# LineFollower.net
KiCad netlist of a schematic drawn in EAGLE
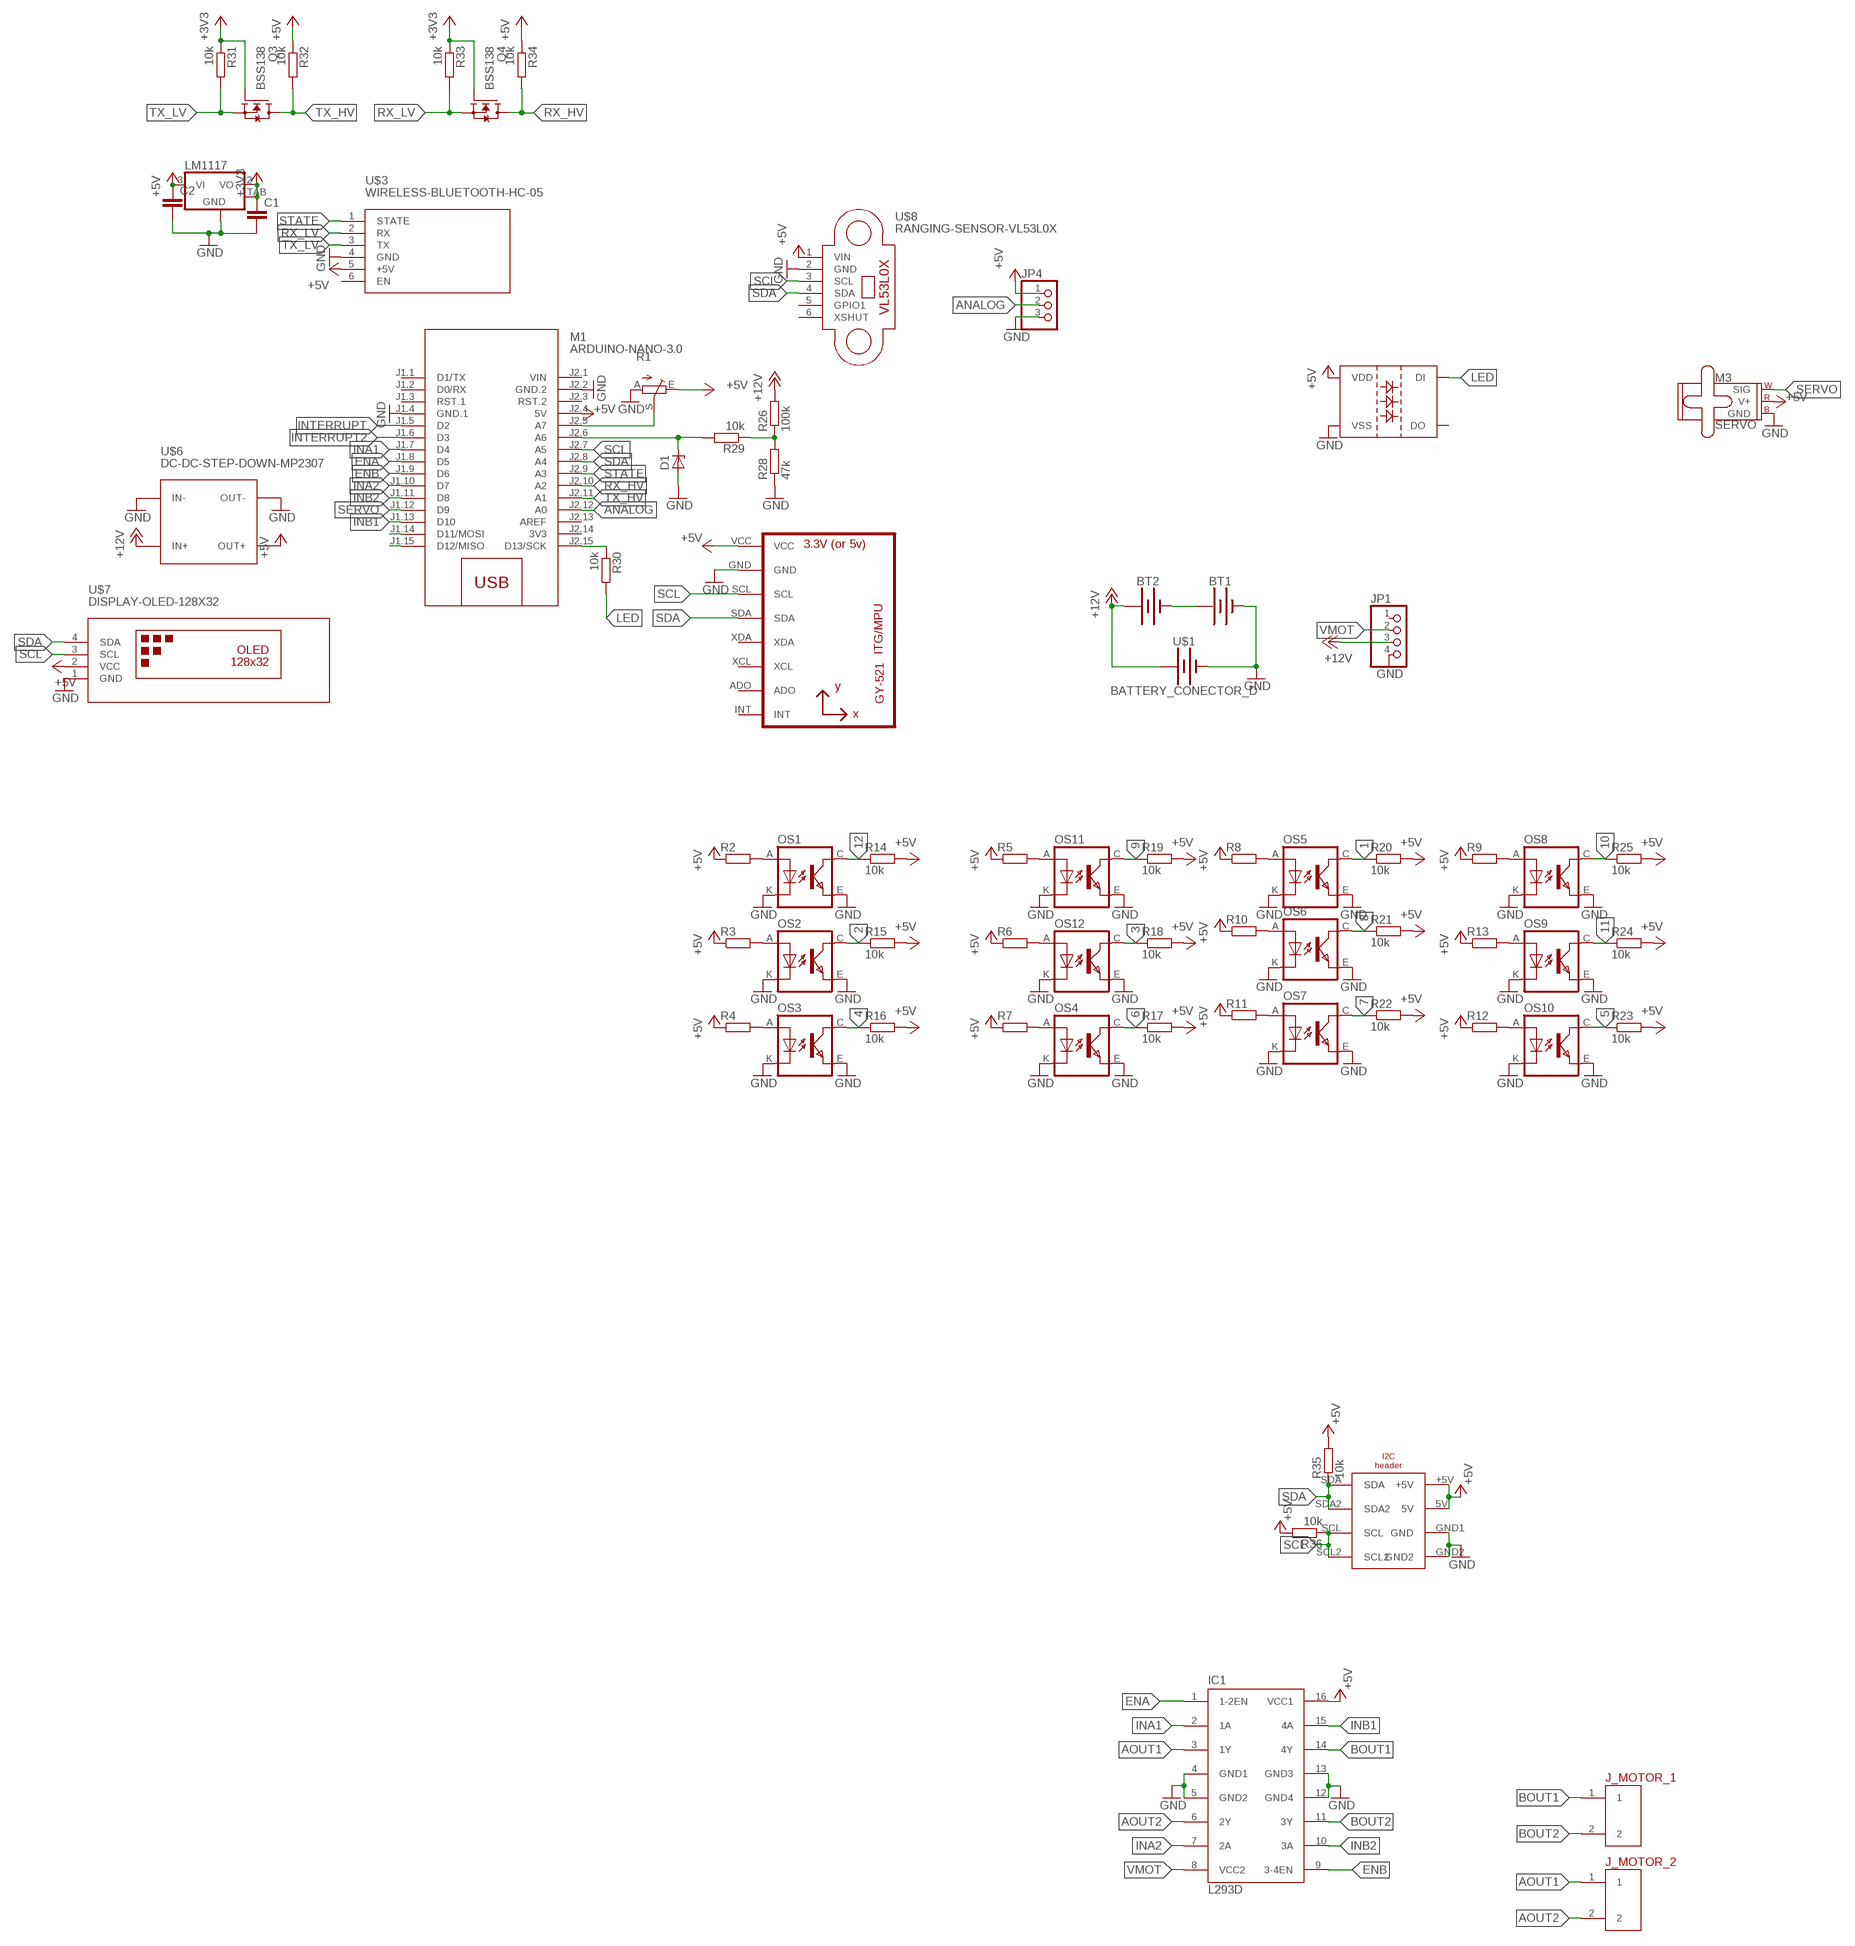
[diagram p0: schematic, sheet 1, part 1 of 2]
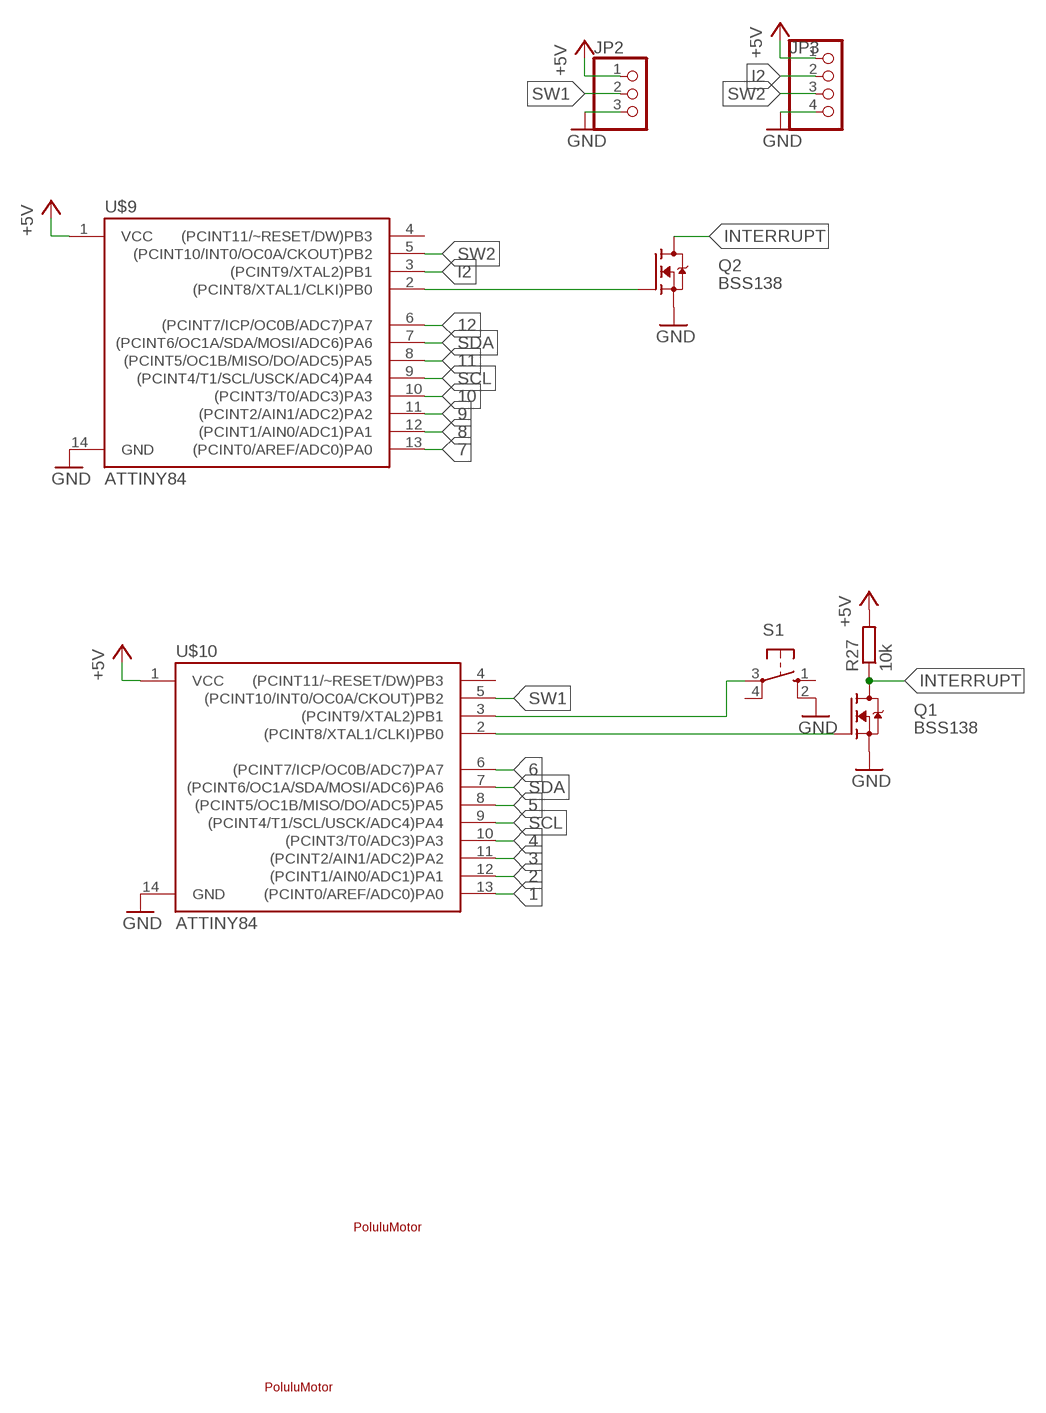
[diagram p1: schematic, sheet 1, part 2 of 2]

(export (version "E")
  (design (tool "Eeschema 10.0.6"))
  (components
    (comp (ref "BT1")
      (value "BATTERY-AA_KIT")
      (footprint "eagle-import:BATTERY-AA-KIT")
      (libsource (lib "eagle-import") (part "BATTERY-AA_KIT"))
    )
    (comp (ref "BT2")
      (value "BATTERY-AA_KIT")
      (footprint "eagle-import:BATTERY-AA-KIT")
      (libsource (lib "eagle-import") (part "BATTERY-AA_KIT"))
    )
    (comp (ref "C1")
      (value "C-EUC1206")
      (footprint "eagle-import:C1206")
      (libsource (lib "eagle-import") (part "C-EUC1206"))
    )
    (comp (ref "C2")
      (value "C-EUC1206")
      (footprint "eagle-import:C1206")
      (libsource (lib "eagle-import") (part "C-EUC1206"))
    )
    (comp (ref "D1")
      (value "ZENER-DIODESOD80C")
      (footprint "eagle-import:SOD80C")
      (libsource (lib "eagle-import") (part "ZENER-DIODESOD80C"))
    )
    (comp (ref "IC1")
      (value "L293D")
      (footprint "eagle-import:L293")
      (libsource (lib "eagle-import") (part "L293D"))
    )
    (comp (ref "JP1")
      (value "PINHD-1X4")
      (footprint "eagle-import:1X04")
      (libsource (lib "eagle-import") (part "PINHD-1X4"))
    )
    (comp (ref "JP2")
      (value "PINHD-1X3")
      (footprint "eagle-import:1X03")
      (libsource (lib "eagle-import") (part "PINHD-1X3"))
    )
    (comp (ref "JP3")
      (value "PINHD-1X4")
      (footprint "eagle-import:1X04")
      (libsource (lib "eagle-import") (part "PINHD-1X4"))
    )
    (comp (ref "JP4")
      (value "PINHD-1X3")
      (footprint "eagle-import:1X03")
      (libsource (lib "eagle-import") (part "PINHD-1X3"))
    )
    (comp (ref "J_MOTOR_1")
      (value "MOTOR_CONNECTOR")
      (footprint "eagle-import:MOTOR_CONNECTOR_FOOTPRINT")
      (libsource (lib "eagle-import") (part "MOTOR_CONNECTOR"))
    )
    (comp (ref "J_MOTOR_2")
      (value "MOTOR_CONNECTOR")
      (footprint "eagle-import:MOTOR_CONNECTOR_FOOTPRINT")
      (libsource (lib "eagle-import") (part "MOTOR_CONNECTOR"))
    )
    (comp (ref "LED1")
      (value "WS2812B")
      (footprint "eagle-import:WS2812B")
      (libsource (lib "eagle-import") (part "WS2812B"))
    )
    (comp (ref "M1")
      (value "ARDUINO-NANO-3.0")
      (footprint "eagle-import:ARDUINO-NANO-3.0")
      (libsource (lib "eagle-import") (part "ARDUINO-NANO-3.0"))
    )
    (comp (ref "M3")
      (value "SERVO")
      (footprint "eagle-import:1X03")
      (libsource (lib "eagle-import") (part "SERVO"))
    )
    (comp (ref "OS1")
      (value "TCRT5000")
      (footprint "eagle-import:TCRT5000")
      (libsource (lib "eagle-import") (part "TCRT5000"))
    )
    (comp (ref "OS2")
      (value "TCRT5000")
      (footprint "eagle-import:TCRT5000")
      (libsource (lib "eagle-import") (part "TCRT5000"))
    )
    (comp (ref "OS3")
      (value "TCRT5000")
      (footprint "eagle-import:TCRT5000")
      (libsource (lib "eagle-import") (part "TCRT5000"))
    )
    (comp (ref "OS4")
      (value "TCRT5000")
      (footprint "eagle-import:TCRT5000")
      (libsource (lib "eagle-import") (part "TCRT5000"))
    )
    (comp (ref "OS5")
      (value "TCRT5000")
      (footprint "eagle-import:TCRT5000")
      (libsource (lib "eagle-import") (part "TCRT5000"))
    )
    (comp (ref "OS6")
      (value "TCRT5000")
      (footprint "eagle-import:TCRT5000")
      (libsource (lib "eagle-import") (part "TCRT5000"))
    )
    (comp (ref "OS7")
      (value "TCRT5000")
      (footprint "eagle-import:TCRT5000")
      (libsource (lib "eagle-import") (part "TCRT5000"))
    )
    (comp (ref "OS8")
      (value "TCRT5000")
      (footprint "eagle-import:TCRT5000")
      (libsource (lib "eagle-import") (part "TCRT5000"))
    )
    (comp (ref "OS9")
      (value "TCRT5000")
      (footprint "eagle-import:TCRT5000")
      (libsource (lib "eagle-import") (part "TCRT5000"))
    )
    (comp (ref "OS10")
      (value "TCRT5000")
      (footprint "eagle-import:TCRT5000")
      (libsource (lib "eagle-import") (part "TCRT5000"))
    )
    (comp (ref "OS11")
      (value "TCRT5000")
      (footprint "eagle-import:TCRT5000")
      (libsource (lib "eagle-import") (part "TCRT5000"))
    )
    (comp (ref "OS12")
      (value "TCRT5000")
      (footprint "eagle-import:TCRT5000")
      (libsource (lib "eagle-import") (part "TCRT5000"))
    )
    (comp (ref "Q1")
      (value "BSS138")
      (footprint "eagle-import:SOT23")
      (fields (field (name "MF") "Fairchild"))
      (libsource (lib "eagle-import") (part "BSS138"))
    )
    (comp (ref "Q2")
      (value "BSS138")
      (footprint "eagle-import:SOT23")
      (fields (field (name "MF") "Fairchild"))
      (libsource (lib "eagle-import") (part "BSS138"))
    )
    (comp (ref "Q3")
      (value "BSS138")
      (footprint "eagle-import:SOT23")
      (fields (field (name "MF") "Fairchild"))
      (libsource (lib "eagle-import") (part "BSS138"))
    )
    (comp (ref "Q4")
      (value "BSS138")
      (footprint "eagle-import:SOT23")
      (fields (field (name "MF") "Fairchild"))
      (libsource (lib "eagle-import") (part "BSS138"))
    )
    (comp (ref "R1")
      (value "TRIM_EU-RJ9W")
      (footprint "eagle-import:RJ9W")
      (libsource (lib "eagle-import") (part "TRIM_EU-RJ9W"))
    )
    (comp (ref "R2")
      (value "R-EU_M1206")
      (footprint "eagle-import:M1206")
      (libsource (lib "eagle-import") (part "R-EU_M1206"))
    )
    (comp (ref "R3")
      (value "R-EU_M1206")
      (footprint "eagle-import:M1206")
      (libsource (lib "eagle-import") (part "R-EU_M1206"))
    )
    (comp (ref "R4")
      (value "R-EU_M1206")
      (footprint "eagle-import:M1206")
      (libsource (lib "eagle-import") (part "R-EU_M1206"))
    )
    (comp (ref "R5")
      (value "R-EU_M1206")
      (footprint "eagle-import:M1206")
      (libsource (lib "eagle-import") (part "R-EU_M1206"))
    )
    (comp (ref "R6")
      (value "R-EU_M1206")
      (footprint "eagle-import:M1206")
      (libsource (lib "eagle-import") (part "R-EU_M1206"))
    )
    (comp (ref "R7")
      (value "R-EU_M1206")
      (footprint "eagle-import:M1206")
      (libsource (lib "eagle-import") (part "R-EU_M1206"))
    )
    (comp (ref "R8")
      (value "R-EU_M1206")
      (footprint "eagle-import:M1206")
      (libsource (lib "eagle-import") (part "R-EU_M1206"))
    )
    (comp (ref "R9")
      (value "R-EU_M1206")
      (footprint "eagle-import:M1206")
      (libsource (lib "eagle-import") (part "R-EU_M1206"))
    )
    (comp (ref "R10")
      (value "R-EU_M1206")
      (footprint "eagle-import:M1206")
      (libsource (lib "eagle-import") (part "R-EU_M1206"))
    )
    (comp (ref "R11")
      (value "R-EU_M1206")
      (footprint "eagle-import:M1206")
      (libsource (lib "eagle-import") (part "R-EU_M1206"))
    )
    (comp (ref "R12")
      (value "R-EU_M1206")
      (footprint "eagle-import:M1206")
      (libsource (lib "eagle-import") (part "R-EU_M1206"))
    )
    (comp (ref "R13")
      (value "R-EU_M1206")
      (footprint "eagle-import:M1206")
      (libsource (lib "eagle-import") (part "R-EU_M1206"))
    )
    (comp (ref "R14")
      (value "10k")
      (footprint "eagle-import:M1206")
      (libsource (lib "eagle-import") (part "R-EU_M1206"))
    )
    (comp (ref "R15")
      (value "10k")
      (footprint "eagle-import:M1206")
      (libsource (lib "eagle-import") (part "R-EU_M1206"))
    )
    (comp (ref "R16")
      (value "10k")
      (footprint "eagle-import:M1206")
      (libsource (lib "eagle-import") (part "R-EU_M1206"))
    )
    (comp (ref "R17")
      (value "10k")
      (footprint "eagle-import:M1206")
      (libsource (lib "eagle-import") (part "R-EU_M1206"))
    )
    (comp (ref "R18")
      (value "10k")
      (footprint "eagle-import:M1206")
      (libsource (lib "eagle-import") (part "R-EU_M1206"))
    )
    (comp (ref "R19")
      (value "10k")
      (footprint "eagle-import:M1206")
      (libsource (lib "eagle-import") (part "R-EU_M1206"))
    )
    (comp (ref "R20")
      (value "10k")
      (footprint "eagle-import:M1206")
      (libsource (lib "eagle-import") (part "R-EU_M1206"))
    )
    (comp (ref "R21")
      (value "10k")
      (footprint "eagle-import:M1206")
      (libsource (lib "eagle-import") (part "R-EU_M1206"))
    )
    (comp (ref "R22")
      (value "10k")
      (footprint "eagle-import:M1206")
      (libsource (lib "eagle-import") (part "R-EU_M1206"))
    )
    (comp (ref "R23")
      (value "10k")
      (footprint "eagle-import:M1206")
      (libsource (lib "eagle-import") (part "R-EU_M1206"))
    )
    (comp (ref "R24")
      (value "10k")
      (footprint "eagle-import:M1206")
      (libsource (lib "eagle-import") (part "R-EU_M1206"))
    )
    (comp (ref "R25")
      (value "10k")
      (footprint "eagle-import:M1206")
      (libsource (lib "eagle-import") (part "R-EU_M1206"))
    )
    (comp (ref "R26")
      (value "100k")
      (footprint "eagle-import:M1206")
      (libsource (lib "eagle-import") (part "R-EU_M1206"))
    )
    (comp (ref "R27")
      (value "10k")
      (footprint "eagle-import:M1206")
      (libsource (lib "eagle-import") (part "R-EU_M1206"))
    )
    (comp (ref "R28")
      (value "47k")
      (footprint "eagle-import:M1206")
      (libsource (lib "eagle-import") (part "R-EU_M1206"))
    )
    (comp (ref "R29")
      (value "10k")
      (footprint "eagle-import:M1206")
      (libsource (lib "eagle-import") (part "R-EU_M1206"))
    )
    (comp (ref "R30")
      (value "10k")
      (footprint "eagle-import:M1206")
      (libsource (lib "eagle-import") (part "R-EU_M1206"))
    )
    (comp (ref "R31")
      (value "10k")
      (footprint "eagle-import:M1206")
      (libsource (lib "eagle-import") (part "R-EU_M1206"))
    )
    (comp (ref "R32")
      (value "10k")
      (footprint "eagle-import:M1206")
      (libsource (lib "eagle-import") (part "R-EU_M1206"))
    )
    (comp (ref "R33")
      (value "10k")
      (footprint "eagle-import:M1206")
      (libsource (lib "eagle-import") (part "R-EU_M1206"))
    )
    (comp (ref "R34")
      (value "10k")
      (footprint "eagle-import:M1206")
      (libsource (lib "eagle-import") (part "R-EU_M1206"))
    )
    (comp (ref "R35")
      (value "10k")
      (footprint "eagle-import:M1206")
      (libsource (lib "eagle-import") (part "R-EU_M1206"))
    )
    (comp (ref "R36")
      (value "10k")
      (footprint "eagle-import:M1206")
      (libsource (lib "eagle-import") (part "R-EU_M1206"))
    )
    (comp (ref "S1")
      (value "10-XX")
      (footprint "eagle-import:B3F-10XX")
      (fields (field (name "MPN") "B3F-1000"))
      (libsource (lib "eagle-import") (part "10-XX"))
    )
    (comp (ref "U$1")
      (value "BATTERY_CONECTOR_D")
      (footprint "eagle-import:BATTERY_CONECTOR_D")
      (libsource (lib "eagle-import") (part "BATTERY_CONECTOR_D"))
    )
    (comp (ref "U$2")
      (value "I2C_HEADER")
      (footprint "eagle-import:I2_HEADER")
      (libsource (lib "eagle-import") (part "I2C_HEADER"))
    )
    (comp (ref "U$3")
      (value "WIRELESS-BLUETOOTH-HC-05")
      (footprint "eagle-import:WIRELESS-BLUETOOTH-HC-05")
      (libsource (lib "eagle-import") (part "WIRELESS-BLUETOOTH-HC-05"))
    )
    (comp (ref "U$4")
      (value "LM1117")
      (footprint "eagle-import:LM1117")
      (libsource (lib "eagle-import") (part "LM1117"))
    )
    (comp (ref "U$6")
      (value "DC-DC-STEP-DOWN-MP2307")
      (footprint "eagle-import:DC-DC-STEP-DOWN-MP2307")
      (libsource (lib "eagle-import") (part "DC-DC-STEP-DOWN-MP2307"))
    )
    (comp (ref "U$7")
      (value "DISPLAY-OLED-128X32")
      (footprint "eagle-import:DISPLAY-OLED-128X32")
      (libsource (lib "eagle-import") (part "DISPLAY-OLED-128X32"))
    )
    (comp (ref "U$8")
      (value "RANGING-SENSOR-VL53L0X")
      (footprint "eagle-import:RANGING-SENSOR-VL53L0X")
      (libsource (lib "eagle-import") (part "RANGING-SENSOR-VL53L0X"))
    )
    (comp (ref "U$9")
      (value "ATTINY84")
      (footprint "eagle-import:SO14")
      (libsource (lib "eagle-import") (part "ATTINY84"))
    )
    (comp (ref "U$10")
      (value "ATTINY84")
      (footprint "eagle-import:SO14")
      (libsource (lib "eagle-import") (part "ATTINY84"))
    )
    (comp (ref "U$12")
      (value "POLULU_MOTOR")
      (footprint "eagle-import:POLULU_MOTOR")
      (libsource (lib "eagle-import") (part "POLULU_MOTOR"))
    )
    (comp (ref "U$13")
      (value "POLULU_MOTOR")
      (footprint "eagle-import:POLULU_MOTOR")
      (libsource (lib "eagle-import") (part "POLULU_MOTOR"))
    )
    (comp (ref "U1")
      (value "MPU-6050MPU6050")
      (footprint "eagle-import:MPU-6050")
      (libsource (lib "eagle-import") (part "MPU-6050MPU6050"))
    )
  )
  (nets
    (net (code "1") (name "+3V3") (class "Default")
      (node (ref "C1") (pin "1") (pinfunction "1_1") (pintype "passive"))
      (node (ref "Q3") (pin "1") (pinfunction "G_1") (pintype "passive"))
      (node (ref "Q4") (pin "1") (pinfunction "G_1") (pintype "passive"))
      (node (ref "R31") (pin "1") (pinfunction "1_1") (pintype "passive"))
      (node (ref "R33") (pin "1") (pinfunction "1_1") (pintype "passive"))
      (node (ref "U$4") (pin "2") (pinfunction "VO_2") (pintype "passive"))
      (node (ref "U$4") (pin "TAB") (pinfunction "OUT_TAB") (pintype "passive"))
    )
    (net (code "2") (name "+5V") (class "Default")
      (node (ref "C2") (pin "1") (pinfunction "1_1") (pintype "passive"))
      (node (ref "IC1") (pin "16") (pinfunction "VCC1_16") (pintype "power_in"))
      (node (ref "JP2") (pin "1") (pinfunction "1_1") (pintype "passive"))
      (node (ref "JP3") (pin "1") (pinfunction "1_1") (pintype "passive"))
      (node (ref "JP4") (pin "1") (pinfunction "1_1") (pintype "passive"))
      (node (ref "LED1") (pin "1") (pinfunction "VDD_1") (pintype "bidirectional"))
      (node (ref "M1") (pin "J2.4") (pinfunction "5V_J2.4") (pintype "power_in"))
      (node (ref "M3") (pin "2") (pinfunction "V+_2") (pintype "bidirectional"))
      (node (ref "R1") (pin "E") (pinfunction "E_E") (pintype "passive"))
      (node (ref "R10") (pin "1") (pinfunction "1_1") (pintype "passive"))
      (node (ref "R11") (pin "1") (pinfunction "1_1") (pintype "passive"))
      (node (ref "R12") (pin "1") (pinfunction "1_1") (pintype "passive"))
      (node (ref "R13") (pin "1") (pinfunction "1_1") (pintype "passive"))
      (node (ref "R14") (pin "2") (pinfunction "2_2") (pintype "passive"))
      (node (ref "R15") (pin "2") (pinfunction "2_2") (pintype "passive"))
      (node (ref "R16") (pin "2") (pinfunction "2_2") (pintype "passive"))
      (node (ref "R17") (pin "2") (pinfunction "2_2") (pintype "passive"))
      (node (ref "R18") (pin "2") (pinfunction "2_2") (pintype "passive"))
      (node (ref "R19") (pin "2") (pinfunction "2_2") (pintype "passive"))
      (node (ref "R2") (pin "1") (pinfunction "1_1") (pintype "passive"))
      (node (ref "R20") (pin "2") (pinfunction "2_2") (pintype "passive"))
      (node (ref "R21") (pin "2") (pinfunction "2_2") (pintype "passive"))
      (node (ref "R22") (pin "2") (pinfunction "2_2") (pintype "passive"))
      (node (ref "R23") (pin "2") (pinfunction "2_2") (pintype "passive"))
      (node (ref "R24") (pin "2") (pinfunction "2_2") (pintype "passive"))
      (node (ref "R25") (pin "2") (pinfunction "2_2") (pintype "passive"))
      (node (ref "R27") (pin "2") (pinfunction "2_2") (pintype "passive"))
      (node (ref "R3") (pin "1") (pinfunction "1_1") (pintype "passive"))
      (node (ref "R32") (pin "1") (pinfunction "1_1") (pintype "passive"))
      (node (ref "R34") (pin "1") (pinfunction "1_1") (pintype "passive"))
      (node (ref "R35") (pin "2") (pinfunction "2_2") (pintype "passive"))
      (node (ref "R36") (pin "2") (pinfunction "2_2") (pintype "passive"))
      (node (ref "R4") (pin "1") (pinfunction "1_1") (pintype "passive"))
      (node (ref "R5") (pin "1") (pinfunction "1_1") (pintype "passive"))
      (node (ref "R6") (pin "1") (pinfunction "1_1") (pintype "passive"))
      (node (ref "R7") (pin "1") (pinfunction "1_1") (pintype "passive"))
      (node (ref "R8") (pin "1") (pinfunction "1_1") (pintype "passive"))
      (node (ref "R9") (pin "1") (pinfunction "1_1") (pintype "passive"))
      (node (ref "U$10") (pin "1") (pinfunction "VCC_1") (pintype "bidirectional"))
      (node (ref "U$2") (pin "+5V") (pinfunction "+5V_+5V") (pintype "bidirectional"))
      (node (ref "U$2") (pin "5V") (pinfunction "5V_5V") (pintype "bidirectional"))
      (node (ref "U$3") (pin "5") (pinfunction "+5V_5") (pintype "power_in"))
      (node (ref "U$4") (pin "3") (pinfunction "VI_3") (pintype "input"))
      (node (ref "U$6") (pin "OUT+") (pinfunction "OUT+_OUT+") (pintype "bidirectional"))
      (node (ref "U$7") (pin "2") (pinfunction "VCC_2") (pintype "power_in"))
      (node (ref "U$8") (pin "1") (pinfunction "VIN_1") (pintype "power_in"))
      (node (ref "U$9") (pin "1") (pinfunction "VCC_1") (pintype "bidirectional"))
      (node (ref "U1") (pin "VCC") (pinfunction "VCC_VCC") (pintype "bidirectional"))
    )
    (net (code "3") (name "+12V") (class "Default")
      (node (ref "BT2") (pin "PWR@1") (pinfunction "+_PWR@1") (pintype "power_in"))
      (node (ref "JP1") (pin "3") (pinfunction "3_3") (pintype "passive"))
      (node (ref "R26") (pin "2") (pinfunction "2_2") (pintype "passive"))
      (node (ref "U$1") (pin "+") (pinfunction "+_+") (pintype "power_in"))
      (node (ref "U$6") (pin "IN+") (pinfunction "IN+_IN+") (pintype "bidirectional"))
    )
    (net (code "4") (name "/3V3") (class "Default")
      (node (ref "M1") (pin "J2.14") (pinfunction "3V3_J2.14") (pintype "power_in"))
    )
    (net (code "5") (name "/VIN") (class "Default")
      (node (ref "M1") (pin "J2.1") (pinfunction "VIN_J2.1") (pintype "power_in"))
    )
    (net (code "6") (name "1") (class "Default")
      (node (ref "OS5") (pin "C") (pinfunction "COLLECTOR_C") (pintype "passive"))
      (node (ref "R20") (pin "1") (pinfunction "1_1") (pintype "passive"))
      (node (ref "U$10") (pin "13") (pinfunction "(PCINT0/AREF/ADC0)PA0_13") (pintype "bidirectional"))
    )
    (net (code "7") (name "2") (class "Default")
      (node (ref "OS2") (pin "C") (pinfunction "COLLECTOR_C") (pintype "passive"))
      (node (ref "R15") (pin "1") (pinfunction "1_1") (pintype "passive"))
      (node (ref "U$10") (pin "12") (pinfunction "(PCINT1/AIN0/ADC1)PA1_12") (pintype "bidirectional"))
    )
    (net (code "8") (name "3") (class "Default")
      (node (ref "OS12") (pin "C") (pinfunction "COLLECTOR_C") (pintype "passive"))
      (node (ref "R18") (pin "1") (pinfunction "1_1") (pintype "passive"))
      (node (ref "U$10") (pin "11") (pinfunction "(PCINT2/AIN1/ADC2)PA2_11") (pintype "bidirectional"))
    )
    (net (code "9") (name "4") (class "Default")
      (node (ref "OS3") (pin "C") (pinfunction "COLLECTOR_C") (pintype "passive"))
      (node (ref "R16") (pin "1") (pinfunction "1_1") (pintype "passive"))
      (node (ref "U$10") (pin "10") (pinfunction "(PCINT3/T0/ADC3)PA3_10") (pintype "bidirectional"))
    )
    (net (code "10") (name "5") (class "Default")
      (node (ref "OS10") (pin "C") (pinfunction "COLLECTOR_C") (pintype "passive"))
      (node (ref "R23") (pin "1") (pinfunction "1_1") (pintype "passive"))
      (node (ref "U$10") (pin "8") (pinfunction "(PCINT5/OC1B/MISO/DO/ADC5)PA5_8") (pintype "bidirectional"))
    )
    (net (code "11") (name "6") (class "Default")
      (node (ref "OS4") (pin "C") (pinfunction "COLLECTOR_C") (pintype "passive"))
      (node (ref "R17") (pin "1") (pinfunction "1_1") (pintype "passive"))
      (node (ref "U$10") (pin "6") (pinfunction "(PCINT7/ICP/OC0B/ADC7)PA7_6") (pintype "bidirectional"))
    )
    (net (code "12") (name "7") (class "Default")
      (node (ref "OS7") (pin "C") (pinfunction "COLLECTOR_C") (pintype "passive"))
      (node (ref "R22") (pin "1") (pinfunction "1_1") (pintype "passive"))
      (node (ref "U$9") (pin "13") (pinfunction "(PCINT0/AREF/ADC0)PA0_13") (pintype "bidirectional"))
    )
    (net (code "13") (name "8") (class "Default")
      (node (ref "OS6") (pin "C") (pinfunction "COLLECTOR_C") (pintype "passive"))
      (node (ref "R21") (pin "1") (pinfunction "1_1") (pintype "passive"))
      (node (ref "U$9") (pin "12") (pinfunction "(PCINT1/AIN0/ADC1)PA1_12") (pintype "bidirectional"))
    )
    (net (code "14") (name "9") (class "Default")
      (node (ref "OS11") (pin "C") (pinfunction "COLLECTOR_C") (pintype "passive"))
      (node (ref "R19") (pin "1") (pinfunction "1_1") (pintype "passive"))
      (node (ref "U$9") (pin "11") (pinfunction "(PCINT2/AIN1/ADC2)PA2_11") (pintype "bidirectional"))
    )
    (net (code "15") (name "10") (class "Default")
      (node (ref "OS8") (pin "C") (pinfunction "COLLECTOR_C") (pintype "passive"))
      (node (ref "R25") (pin "1") (pinfunction "1_1") (pintype "passive"))
      (node (ref "U$9") (pin "10") (pinfunction "(PCINT3/T0/ADC3)PA3_10") (pintype "bidirectional"))
    )
    (net (code "16") (name "11") (class "Default")
      (node (ref "OS9") (pin "C") (pinfunction "COLLECTOR_C") (pintype "passive"))
      (node (ref "R24") (pin "1") (pinfunction "1_1") (pintype "passive"))
      (node (ref "U$9") (pin "8") (pinfunction "(PCINT5/OC1B/MISO/DO/ADC5)PA5_8") (pintype "bidirectional"))
    )
    (net (code "17") (name "12") (class "Default")
      (node (ref "OS1") (pin "C") (pinfunction "COLLECTOR_C") (pintype "passive"))
      (node (ref "R14") (pin "1") (pinfunction "1_1") (pintype "passive"))
      (node (ref "U$9") (pin "6") (pinfunction "(PCINT7/ICP/OC0B/ADC7)PA7_6") (pintype "bidirectional"))
    )
    (net (code "18") (name "ANALOG") (class "Default")
      (node (ref "JP4") (pin "2") (pinfunction "2_2") (pintype "passive"))
      (node (ref "M1") (pin "J2.12") (pinfunction "A0_J2.12") (pintype "bidirectional"))
    )
    (net (code "19") (name "AOUT1") (class "Default")
      (node (ref "IC1") (pin "3") (pinfunction "1Y_3") (pintype "output"))
      (node (ref "J_MOTOR_2") (pin "1") (pinfunction "1_1") (pintype "bidirectional"))
    )
    (net (code "20") (name "AOUT2") (class "Default")
      (node (ref "IC1") (pin "6") (pinfunction "2Y_6") (pintype "output"))
      (node (ref "J_MOTOR_2") (pin "2") (pinfunction "2_2") (pintype "bidirectional"))
    )
    (net (code "21") (name "BOUT1") (class "Default")
      (node (ref "IC1") (pin "14") (pinfunction "4Y_14") (pintype "output"))
      (node (ref "J_MOTOR_1") (pin "1") (pinfunction "1_1") (pintype "bidirectional"))
    )
    (net (code "22") (name "BOUT2") (class "Default")
      (node (ref "IC1") (pin "11") (pinfunction "3Y_11") (pintype "output"))
      (node (ref "J_MOTOR_1") (pin "2") (pinfunction "2_2") (pintype "bidirectional"))
    )
    (net (code "23") (name "ENA") (class "Default")
      (node (ref "IC1") (pin "1") (pinfunction "1-2EN_1") (pintype "input"))
      (node (ref "M1") (pin "J1.8") (pinfunction "D5_J1.8") (pintype "bidirectional"))
    )
    (net (code "24") (name "ENB") (class "Default")
      (node (ref "IC1") (pin "9") (pinfunction "3-4EN_9") (pintype "input"))
      (node (ref "M1") (pin "J1.9") (pinfunction "D6_J1.9") (pintype "bidirectional"))
    )
    (net (code "25") (name "GND") (class "Default")
      (node (ref "BT1") (pin "GND@1") (pinfunction "-_GND@1") (pintype "power_in"))
      (node (ref "C1") (pin "2") (pinfunction "2_2") (pintype "passive"))
      (node (ref "C2") (pin "2") (pinfunction "2_2") (pintype "passive"))
      (node (ref "D1") (pin "A") (pinfunction "A_A") (pintype "passive"))
      (node (ref "IC1") (pin "12") (pinfunction "GND4_12") (pintype "power_in"))
      (node (ref "IC1") (pin "13") (pinfunction "GND3_13") (pintype "power_in"))
      (node (ref "IC1") (pin "4") (pinfunction "GND1_4") (pintype "power_in"))
      (node (ref "IC1") (pin "5") (pinfunction "GND2_5") (pintype "power_in"))
      (node (ref "JP1") (pin "4") (pinfunction "4_4") (pintype "passive"))
      (node (ref "JP2") (pin "3") (pinfunction "3_3") (pintype "passive"))
      (node (ref "JP3") (pin "4") (pinfunction "4_4") (pintype "passive"))
      (node (ref "JP4") (pin "3") (pinfunction "3_3") (pintype "passive"))
      (node (ref "LED1") (pin "3") (pinfunction "VSS_3") (pintype "bidirectional"))
      (node (ref "M1") (pin "J1.4") (pinfunction "GND.1_J1.4") (pintype "power_in"))
      (node (ref "M1") (pin "J2.2") (pinfunction "GND.2_J2.2") (pintype "power_in"))
      (node (ref "M3") (pin "3") (pinfunction "GND_3") (pintype "bidirectional"))
      (node (ref "OS1") (pin "E") (pinfunction "EMITTER_E") (pintype "passive"))
      (node (ref "OS1") (pin "K") (pinfunction "CATHODE_K") (pintype "passive"))
      (node (ref "OS10") (pin "E") (pinfunction "EMITTER_E") (pintype "passive"))
      (node (ref "OS10") (pin "K") (pinfunction "CATHODE_K") (pintype "passive"))
      (node (ref "OS11") (pin "E") (pinfunction "EMITTER_E") (pintype "passive"))
      (node (ref "OS11") (pin "K") (pinfunction "CATHODE_K") (pintype "passive"))
      (node (ref "OS12") (pin "E") (pinfunction "EMITTER_E") (pintype "passive"))
      (node (ref "OS12") (pin "K") (pinfunction "CATHODE_K") (pintype "passive"))
      (node (ref "OS2") (pin "E") (pinfunction "EMITTER_E") (pintype "passive"))
      (node (ref "OS2") (pin "K") (pinfunction "CATHODE_K") (pintype "passive"))
      (node (ref "OS3") (pin "E") (pinfunction "EMITTER_E") (pintype "passive"))
      (node (ref "OS3") (pin "K") (pinfunction "CATHODE_K") (pintype "passive"))
      (node (ref "OS4") (pin "E") (pinfunction "EMITTER_E") (pintype "passive"))
      (node (ref "OS4") (pin "K") (pinfunction "CATHODE_K") (pintype "passive"))
      (node (ref "OS5") (pin "E") (pinfunction "EMITTER_E") (pintype "passive"))
      (node (ref "OS5") (pin "K") (pinfunction "CATHODE_K") (pintype "passive"))
      (node (ref "OS6") (pin "E") (pinfunction "EMITTER_E") (pintype "passive"))
      (node (ref "OS6") (pin "K") (pinfunction "CATHODE_K") (pintype "passive"))
      (node (ref "OS7") (pin "E") (pinfunction "EMITTER_E") (pintype "passive"))
      (node (ref "OS7") (pin "K") (pinfunction "CATHODE_K") (pintype "passive"))
      (node (ref "OS8") (pin "E") (pinfunction "EMITTER_E") (pintype "passive"))
      (node (ref "OS8") (pin "K") (pinfunction "CATHODE_K") (pintype "passive"))
      (node (ref "OS9") (pin "E") (pinfunction "EMITTER_E") (pintype "passive"))
      (node (ref "OS9") (pin "K") (pinfunction "CATHODE_K") (pintype "passive"))
      (node (ref "Q1") (pin "2") (pinfunction "S_2") (pintype "passive"))
      (node (ref "Q2") (pin "2") (pinfunction "S_2") (pintype "passive"))
      (node (ref "R1") (pin "A") (pinfunction "A_A") (pintype "passive"))
      (node (ref "R28") (pin "1") (pinfunction "1_1") (pintype "passive"))
      (node (ref "S1") (pin "2") (pinfunction "S1_2") (pintype "passive"))
      (node (ref "U$1") (pin "-") (pinfunction "-_-") (pintype "power_in"))
      (node (ref "U$10") (pin "14") (pinfunction "GND_14") (pintype "bidirectional"))
      (node (ref "U$2") (pin "GND1") (pinfunction "GND_GND1") (pintype "bidirectional"))
      (node (ref "U$2") (pin "GND2") (pinfunction "GND2_GND2") (pintype "bidirectional"))
      (node (ref "U$3") (pin "4") (pinfunction "GND_4") (pintype "power_in"))
      (node (ref "U$4") (pin "1") (pinfunction "GND_1") (pintype "passive"))
      (node (ref "U$6") (pin "IN-") (pinfunction "IN-_IN-") (pintype "bidirectional"))
      (node (ref "U$6") (pin "OUT-") (pinfunction "OUT-_OUT-") (pintype "bidirectional"))
      (node (ref "U$7") (pin "1") (pinfunction "GND_1") (pintype "power_in"))
      (node (ref "U$8") (pin "2") (pinfunction "GND_2") (pintype "power_in"))
      (node (ref "U$9") (pin "14") (pinfunction "GND_14") (pintype "bidirectional"))
      (node (ref "U1") (pin "GND") (pinfunction "GND_GND") (pintype "bidirectional"))
    )
    (net (code "26") (name "I2") (class "Default")
      (node (ref "JP3") (pin "2") (pinfunction "2_2") (pintype "passive"))
      (node (ref "U$9") (pin "3") (pinfunction "(PCINT9/XTAL2)PB1_3") (pintype "bidirectional"))
    )
    (net (code "27") (name "INA1") (class "Default")
      (node (ref "IC1") (pin "2") (pinfunction "1A_2") (pintype "input"))
      (node (ref "M1") (pin "J1.7") (pinfunction "D4_J1.7") (pintype "bidirectional"))
    )
    (net (code "28") (name "INA2") (class "Default")
      (node (ref "IC1") (pin "7") (pinfunction "2A_7") (pintype "input"))
      (node (ref "M1") (pin "J1.10") (pinfunction "D7_J1.10") (pintype "bidirectional"))
    )
    (net (code "29") (name "INB1") (class "Default")
      (node (ref "IC1") (pin "15") (pinfunction "4A_15") (pintype "input"))
      (node (ref "M1") (pin "J1.13") (pinfunction "D10_J1.13") (pintype "bidirectional"))
    )
    (net (code "30") (name "INB2") (class "Default")
      (node (ref "IC1") (pin "10") (pinfunction "3A_10") (pintype "input"))
      (node (ref "M1") (pin "J1.11") (pinfunction "D8_J1.11") (pintype "bidirectional"))
    )
    (net (code "31") (name "INTERRUPT") (class "Default")
      (node (ref "M1") (pin "J1.5") (pinfunction "D2_J1.5") (pintype "bidirectional"))
      (node (ref "Q1") (pin "3") (pinfunction "D_3") (pintype "passive"))
      (node (ref "Q2") (pin "3") (pinfunction "D_3") (pintype "passive"))
      (node (ref "R27") (pin "1") (pinfunction "1_1") (pintype "passive"))
    )
    (net (code "32") (name "INTERRUPT2") (class "Default")
      (node (ref "M1") (pin "J1.6") (pinfunction "D3_J1.6") (pintype "bidirectional"))
    )
    (net (code "33") (name "LED") (class "Default")
      (node (ref "LED1") (pin "4") (pinfunction "DI_4") (pintype "bidirectional"))
      (node (ref "R30") (pin "2") (pinfunction "2_2") (pintype "passive"))
    )
    (net (code "34") (name "Net-(BT1-+)") (class "Default")
      (node (ref "BT1") (pin "PWR@1") (pinfunction "+_PWR@1") (pintype "power_in"))
      (node (ref "BT2") (pin "GND@1") (pinfunction "-_GND@1") (pintype "power_in"))
    )
    (net (code "35") (name "Net-(M1-A6)") (class "Default")
      (node (ref "D1") (pin "C") (pinfunction "C_C") (pintype "passive"))
      (node (ref "M1") (pin "J2.6") (pinfunction "A6_J2.6") (pintype "bidirectional"))
      (node (ref "R29") (pin "2") (pinfunction "2_2") (pintype "passive"))
    )
    (net (code "36") (name "Net-(M1-A7)") (class "Default")
      (node (ref "M1") (pin "J2.5") (pinfunction "A7_J2.5") (pintype "bidirectional"))
      (node (ref "R1") (pin "S") (pinfunction "S_S") (pintype "passive"))
    )
    (net (code "37") (name "Net-(M1-D13{slash}SCK)") (class "Default")
      (node (ref "M1") (pin "J2.15") (pinfunction "D13/SCK_J2.15") (pintype "bidirectional"))
      (node (ref "R30") (pin "1") (pinfunction "1_1") (pintype "passive"))
    )
    (net (code "38") (name "Net-(OS1-ANODE)") (class "Default")
      (node (ref "OS1") (pin "A") (pinfunction "ANODE_A") (pintype "passive"))
      (node (ref "R2") (pin "2") (pinfunction "2_2") (pintype "passive"))
    )
    (net (code "39") (name "Net-(OS2-ANODE)") (class "Default")
      (node (ref "OS2") (pin "A") (pinfunction "ANODE_A") (pintype "passive"))
      (node (ref "R3") (pin "2") (pinfunction "2_2") (pintype "passive"))
    )
    (net (code "40") (name "Net-(OS3-ANODE)") (class "Default")
      (node (ref "OS3") (pin "A") (pinfunction "ANODE_A") (pintype "passive"))
      (node (ref "R4") (pin "2") (pinfunction "2_2") (pintype "passive"))
    )
    (net (code "41") (name "Net-(OS4-ANODE)") (class "Default")
      (node (ref "OS4") (pin "A") (pinfunction "ANODE_A") (pintype "passive"))
      (node (ref "R7") (pin "2") (pinfunction "2_2") (pintype "passive"))
    )
    (net (code "42") (name "Net-(OS5-ANODE)") (class "Default")
      (node (ref "OS5") (pin "A") (pinfunction "ANODE_A") (pintype "passive"))
      (node (ref "R8") (pin "2") (pinfunction "2_2") (pintype "passive"))
    )
    (net (code "43") (name "Net-(OS6-ANODE)") (class "Default")
      (node (ref "OS6") (pin "A") (pinfunction "ANODE_A") (pintype "passive"))
      (node (ref "R10") (pin "2") (pinfunction "2_2") (pintype "passive"))
    )
    (net (code "44") (name "Net-(OS7-ANODE)") (class "Default")
      (node (ref "OS7") (pin "A") (pinfunction "ANODE_A") (pintype "passive"))
      (node (ref "R11") (pin "2") (pinfunction "2_2") (pintype "passive"))
    )
    (net (code "45") (name "Net-(OS8-ANODE)") (class "Default")
      (node (ref "OS8") (pin "A") (pinfunction "ANODE_A") (pintype "passive"))
      (node (ref "R9") (pin "2") (pinfunction "2_2") (pintype "passive"))
    )
    (net (code "46") (name "Net-(OS9-ANODE)") (class "Default")
      (node (ref "OS9") (pin "A") (pinfunction "ANODE_A") (pintype "passive"))
      (node (ref "R13") (pin "2") (pinfunction "2_2") (pintype "passive"))
    )
    (net (code "47") (name "Net-(OS10-ANODE)") (class "Default")
      (node (ref "OS10") (pin "A") (pinfunction "ANODE_A") (pintype "passive"))
      (node (ref "R12") (pin "2") (pinfunction "2_2") (pintype "passive"))
    )
    (net (code "48") (name "Net-(OS11-ANODE)") (class "Default")
      (node (ref "OS11") (pin "A") (pinfunction "ANODE_A") (pintype "passive"))
      (node (ref "R5") (pin "2") (pinfunction "2_2") (pintype "passive"))
    )
    (net (code "49") (name "Net-(OS12-ANODE)") (class "Default")
      (node (ref "OS12") (pin "A") (pinfunction "ANODE_A") (pintype "passive"))
      (node (ref "R6") (pin "2") (pinfunction "2_2") (pintype "passive"))
    )
    (net (code "50") (name "Net-(Q1-G)") (class "Default")
      (node (ref "Q1") (pin "1") (pinfunction "G_1") (pintype "passive"))
      (node (ref "U$10") (pin "2") (pinfunction "(PCINT8/XTAL1/CLKI)PB0_2") (pintype "bidirectional"))
    )
    (net (code "51") (name "Net-(Q2-G)") (class "Default")
      (node (ref "Q2") (pin "1") (pinfunction "G_1") (pintype "passive"))
      (node (ref "U$9") (pin "2") (pinfunction "(PCINT8/XTAL1/CLKI)PB0_2") (pintype "bidirectional"))
    )
    (net (code "52") (name "Net-(R26-Pad1)") (class "Default")
      (node (ref "R26") (pin "1") (pinfunction "1_1") (pintype "passive"))
      (node (ref "R28") (pin "2") (pinfunction "2_2") (pintype "passive"))
      (node (ref "R29") (pin "1") (pinfunction "1_1") (pintype "passive"))
    )
    (net (code "53") (name "Net-(S1-P)") (class "Default")
      (node (ref "S1") (pin "3") (pinfunction "P_3") (pintype "passive"))
      (node (ref "U$10") (pin "3") (pinfunction "(PCINT9/XTAL2)PB1_3") (pintype "bidirectional"))
    )
    (net (code "54") (name "RX_HV") (class "Default")
      (node (ref "M1") (pin "J2.10") (pinfunction "A2_J2.10") (pintype "bidirectional"))
      (node (ref "Q4") (pin "3") (pinfunction "D_3") (pintype "passive"))
      (node (ref "R34") (pin "2") (pinfunction "2_2") (pintype "passive"))
    )
    (net (code "55") (name "RX_LV") (class "Default")
      (node (ref "Q4") (pin "2") (pinfunction "S_2") (pintype "passive"))
      (node (ref "R33") (pin "2") (pinfunction "2_2") (pintype "passive"))
      (node (ref "U$3") (pin "2") (pinfunction "RX_2") (pintype "bidirectional"))
    )
    (net (code "56") (name "SCL") (class "Default")
      (node (ref "M1") (pin "J2.7") (pinfunction "A5_J2.7") (pintype "bidirectional"))
      (node (ref "R36") (pin "1") (pinfunction "1_1") (pintype "passive"))
      (node (ref "U$10") (pin "9") (pinfunction "(PCINT4/T1/SCL/USCK/ADC4)PA4_9") (pintype "bidirectional"))
      (node (ref "U$2") (pin "SCL") (pinfunction "SCL_SCL") (pintype "bidirectional"))
      (node (ref "U$2") (pin "SCL2") (pinfunction "SCL2_SCL2") (pintype "bidirectional"))
      (node (ref "U$7") (pin "3") (pinfunction "SCL_3") (pintype "bidirectional"))
      (node (ref "U$8") (pin "3") (pinfunction "SCL_3") (pintype "bidirectional"))
      (node (ref "U$9") (pin "9") (pinfunction "(PCINT4/T1/SCL/USCK/ADC4)PA4_9") (pintype "bidirectional"))
      (node (ref "U1") (pin "SCL") (pinfunction "SCL_SCL") (pintype "bidirectional"))
    )
    (net (code "57") (name "SDA") (class "Default")
      (node (ref "M1") (pin "J2.8") (pinfunction "A4_J2.8") (pintype "bidirectional"))
      (node (ref "R35") (pin "1") (pinfunction "1_1") (pintype "passive"))
      (node (ref "U$10") (pin "7") (pinfunction "(PCINT6/OC1A/SDA/MOSI/ADC6)PA6_7") (pintype "bidirectional"))
      (node (ref "U$2") (pin "SDA") (pinfunction "SDA_SDA") (pintype "bidirectional"))
      (node (ref "U$2") (pin "SDA2") (pinfunction "SDA2_SDA2") (pintype "bidirectional"))
      (node (ref "U$7") (pin "4") (pinfunction "SDA_4") (pintype "bidirectional"))
      (node (ref "U$8") (pin "4") (pinfunction "SDA_4") (pintype "bidirectional"))
      (node (ref "U$9") (pin "7") (pinfunction "(PCINT6/OC1A/SDA/MOSI/ADC6)PA6_7") (pintype "bidirectional"))
      (node (ref "U1") (pin "SDA") (pinfunction "SDA_SDA") (pintype "bidirectional"))
    )
    (net (code "58") (name "SERVO") (class "Default")
      (node (ref "M1") (pin "J1.12") (pinfunction "D9_J1.12") (pintype "bidirectional"))
      (node (ref "M3") (pin "1") (pinfunction "SIG_1") (pintype "bidirectional"))
    )
    (net (code "59") (name "STATE") (class "Default")
      (node (ref "M1") (pin "J2.9") (pinfunction "A3_J2.9") (pintype "bidirectional"))
      (node (ref "U$3") (pin "1") (pinfunction "STATE_1") (pintype "bidirectional"))
    )
    (net (code "60") (name "SW1") (class "Default")
      (node (ref "JP2") (pin "2") (pinfunction "2_2") (pintype "passive"))
      (node (ref "U$10") (pin "5") (pinfunction "(PCINT10/INT0/OC0A/CKOUT)PB2_5") (pintype "bidirectional"))
    )
    (net (code "61") (name "SW2") (class "Default")
      (node (ref "JP3") (pin "3") (pinfunction "3_3") (pintype "passive"))
      (node (ref "U$9") (pin "5") (pinfunction "(PCINT10/INT0/OC0A/CKOUT)PB2_5") (pintype "bidirectional"))
    )
    (net (code "62") (name "TX_HV") (class "Default")
      (node (ref "M1") (pin "J2.11") (pinfunction "A1_J2.11") (pintype "bidirectional"))
      (node (ref "Q3") (pin "3") (pinfunction "D_3") (pintype "passive"))
      (node (ref "R32") (pin "2") (pinfunction "2_2") (pintype "passive"))
    )
    (net (code "63") (name "TX_LV") (class "Default")
      (node (ref "Q3") (pin "2") (pinfunction "S_2") (pintype "passive"))
      (node (ref "R31") (pin "2") (pinfunction "2_2") (pintype "passive"))
      (node (ref "U$3") (pin "3") (pinfunction "TX_3") (pintype "bidirectional"))
    )
    (net (code "64") (name "VMOT") (class "Default")
      (node (ref "IC1") (pin "8") (pinfunction "VCC2_8") (pintype "power_in"))
      (node (ref "JP1") (pin "2") (pinfunction "2_2") (pintype "passive"))
    )
    (net (code "65") (name "unconnected-(JP1-Pad1)") (class "Default")
      (node (ref "JP1") (pin "1") (pinfunction "1_1") (pintype "passive"))
    )
    (net (code "66") (name "unconnected-(LED1-DO-Pad2)") (class "Default")
      (node (ref "LED1") (pin "2") (pinfunction "DO_2") (pintype "bidirectional"))
    )
    (net (code "67") (name "unconnected-(M1-AREF-PadJ2.13)") (class "Default")
      (node (ref "M1") (pin "J2.13") (pinfunction "AREF_J2.13") (pintype "bidirectional"))
    )
    (net (code "68") (name "unconnected-(M1-D0{slash}RX-PadJ1.2)") (class "Default")
      (node (ref "M1") (pin "J1.2") (pinfunction "D0/RX_J1.2") (pintype "bidirectional"))
    )
    (net (code "69") (name "unconnected-(M1-D1{slash}TX-PadJ1.1)") (class "Default")
      (node (ref "M1") (pin "J1.1") (pinfunction "D1/TX_J1.1") (pintype "bidirectional"))
    )
    (net (code "70") (name "unconnected-(M1-D11{slash}MOSI-PadJ1.14)") (class "Default")
      (node (ref "M1") (pin "J1.14") (pinfunction "D11/MOSI_J1.14") (pintype "bidirectional"))
    )
    (net (code "71") (name "unconnected-(M1-D12{slash}MISO-PadJ1.15)") (class "Default")
      (node (ref "M1") (pin "J1.15") (pinfunction "D12/MISO_J1.15") (pintype "bidirectional"))
    )
    (net (code "72") (name "unconnected-(M1-RST.1-PadJ1.3)") (class "Default")
      (node (ref "M1") (pin "J1.3") (pinfunction "RST.1_J1.3") (pintype "bidirectional"))
    )
    (net (code "73") (name "unconnected-(M1-RST.2-PadJ2.3)") (class "Default")
      (node (ref "M1") (pin "J2.3") (pinfunction "RST.2_J2.3") (pintype "bidirectional"))
    )
    (net (code "74") (name "unconnected-(S1-P1-Pad4)") (class "Default")
      (node (ref "S1") (pin "4") (pinfunction "P1_4") (pintype "passive"))
    )
    (net (code "75") (name "unconnected-(S1-S-Pad1)") (class "Default")
      (node (ref "S1") (pin "1") (pinfunction "S_1") (pintype "passive"))
    )
    (net (code "76") (name "unconnected-(U$3-EN-Pad6)") (class "Default")
      (node (ref "U$3") (pin "6") (pinfunction "EN_6") (pintype "bidirectional"))
    )
    (net (code "77") (name "unconnected-(U$8-GPIO1-Pad5)") (class "Default")
      (node (ref "U$8") (pin "5") (pinfunction "GPIO1_5") (pintype "bidirectional"))
    )
    (net (code "78") (name "unconnected-(U$8-XSHUT-Pad6)") (class "Default")
      (node (ref "U$8") (pin "6") (pinfunction "XSHUT_6") (pintype "bidirectional"))
    )
    (net (code "79") (name "unconnected-(U$9-(PCINT11{slash}~{RESET{slash}DW})PB3-Pad4)") (class "Default")
      (node (ref "U$9") (pin "4") (pinfunction "(PCINT11/~{RESET/DW})PB3_4") (pintype "bidirectional"))
    )
    (net (code "80") (name "unconnected-(U$10-(PCINT11{slash}~{RESET{slash}DW})PB3-Pad4)") (class "Default")
      (node (ref "U$10") (pin "4") (pinfunction "(PCINT11/~{RESET/DW})PB3_4") (pintype "bidirectional"))
    )
    (net (code "81") (name "unconnected-(U1-PadADO)") (class "Default")
      (node (ref "U1") (pin "ADO") (pinfunction "ADO_ADO") (pintype "bidirectional"))
    )
    (net (code "82") (name "unconnected-(U1-PadINT)") (class "Default")
      (node (ref "U1") (pin "INT") (pinfunction "INT_INT") (pintype "bidirectional"))
    )
    (net (code "83") (name "unconnected-(U1-PadXCL)") (class "Default")
      (node (ref "U1") (pin "XCL") (pinfunction "XCL_XCL") (pintype "bidirectional"))
    )
    (net (code "84") (name "unconnected-(U1-PadXDA)") (class "Default")
      (node (ref "U1") (pin "XDA") (pinfunction "XDA_XDA") (pintype "bidirectional"))
    )
  )
)
